# Senser_ver_1.net
KiCad netlist of a schematic drawn in EAGLE
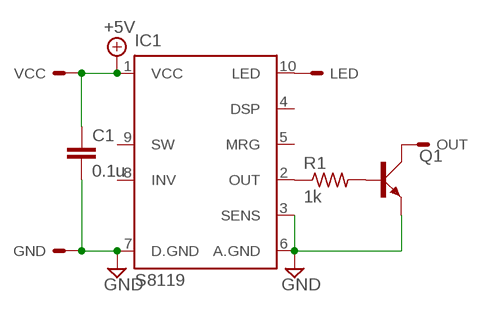
[diagram p0: schematic, sheet 1]

(export (version "E")
  (design (tool "Eeschema 10.0.6"))
  (components
    (comp (ref "C1")
      (value "0.1u")
      (footprint "eagle-import:C1608")
      (libsource (lib "eagle-import") (part "CC1608"))
    )
    (comp (ref "GND")
      (value "PAD")
      (footprint "eagle-import:PAD")
      (libsource (lib "eagle-import") (part "PAD"))
    )
    (comp (ref "IC1")
      (value "S8119")
      (footprint "eagle-import:S8119")
      (libsource (lib "eagle-import") (part "S8119"))
    )
    (comp (ref "LED")
      (value "PAD")
      (footprint "eagle-import:PAD")
      (libsource (lib "eagle-import") (part "PAD"))
    )
    (comp (ref "OUT")
      (value "PAD")
      (footprint "eagle-import:PAD")
      (libsource (lib "eagle-import") (part "PAD"))
    )
    (comp (ref "Q1")
      (value "2SC2712")
      (footprint "eagle-import:SOT23")
      (libsource (lib "eagle-import") (part "2SC1815SOT"))
    )
    (comp (ref "R1")
      (value "1k")
      (footprint "eagle-import:R1608")
      (libsource (lib "eagle-import") (part "R-US_R1608"))
    )
    (comp (ref "VCC")
      (value "PAD")
      (footprint "eagle-import:PAD")
      (libsource (lib "eagle-import") (part "PAD"))
    )
  )
  (nets
    (net (code "1") (name "+5V") (class "Default")
      (node (ref "C1") (pin "1") (pinfunction "1_1") (pintype "passive"))
      (node (ref "IC1") (pin "1") (pinfunction "VCC_1") (pintype "power_in"))
      (node (ref "VCC") (pin "2") (pinfunction "S_2") (pintype "passive"))
    )
    (net (code "2") (name "GND") (class "Default")
      (node (ref "C1") (pin "2") (pinfunction "2_2") (pintype "passive"))
      (node (ref "GND") (pin "2") (pinfunction "S_2") (pintype "passive"))
      (node (ref "IC1") (pin "3") (pinfunction "SENS_3") (pintype "input"))
      (node (ref "IC1") (pin "6") (pinfunction "A.GND_6") (pintype "power_in"))
      (node (ref "IC1") (pin "7") (pinfunction "D.GND_7") (pintype "power_in"))
      (node (ref "Q1") (pin "2") (pinfunction "E_2") (pintype "passive"))
    )
    (net (code "3") (name "Net-(IC1-LED)") (class "Default")
      (node (ref "IC1") (pin "10") (pinfunction "LED_10") (pintype "output"))
      (node (ref "LED") (pin "2") (pinfunction "S_2") (pintype "passive"))
    )
    (net (code "4") (name "Net-(IC1-OUT)") (class "Default")
      (node (ref "IC1") (pin "2") (pinfunction "OUT_2") (pintype "output"))
      (node (ref "R1") (pin "1") (pinfunction "1_1") (pintype "passive"))
    )
    (net (code "5") (name "Net-(OUT-S)") (class "Default")
      (node (ref "OUT") (pin "2") (pinfunction "S_2") (pintype "passive"))
      (node (ref "Q1") (pin "3") (pinfunction "C_3") (pintype "passive"))
    )
    (net (code "6") (name "Net-(Q1-B)") (class "Default")
      (node (ref "Q1") (pin "1") (pinfunction "B_1") (pintype "passive"))
      (node (ref "R1") (pin "2") (pinfunction "2_2") (pintype "passive"))
    )
    (net (code "7") (name "unconnected-(IC1-DSP-Pad4)") (class "Default")
      (node (ref "IC1") (pin "4") (pinfunction "DSP_4") (pintype "output"))
    )
    (net (code "8") (name "unconnected-(IC1-INV-Pad8)") (class "Default")
      (node (ref "IC1") (pin "8") (pinfunction "INV_8") (pintype "input"))
    )
    (net (code "9") (name "unconnected-(IC1-MRG-Pad5)") (class "Default")
      (node (ref "IC1") (pin "5") (pinfunction "MRG_5") (pintype "output"))
    )
    (net (code "10") (name "unconnected-(IC1-SW-Pad9)") (class "Default")
      (node (ref "IC1") (pin "9") (pinfunction "SW_9") (pintype "input"))
    )
  )
)
